# Speedy_V2_1.net
KiCad netlist of a schematic drawn in EAGLE
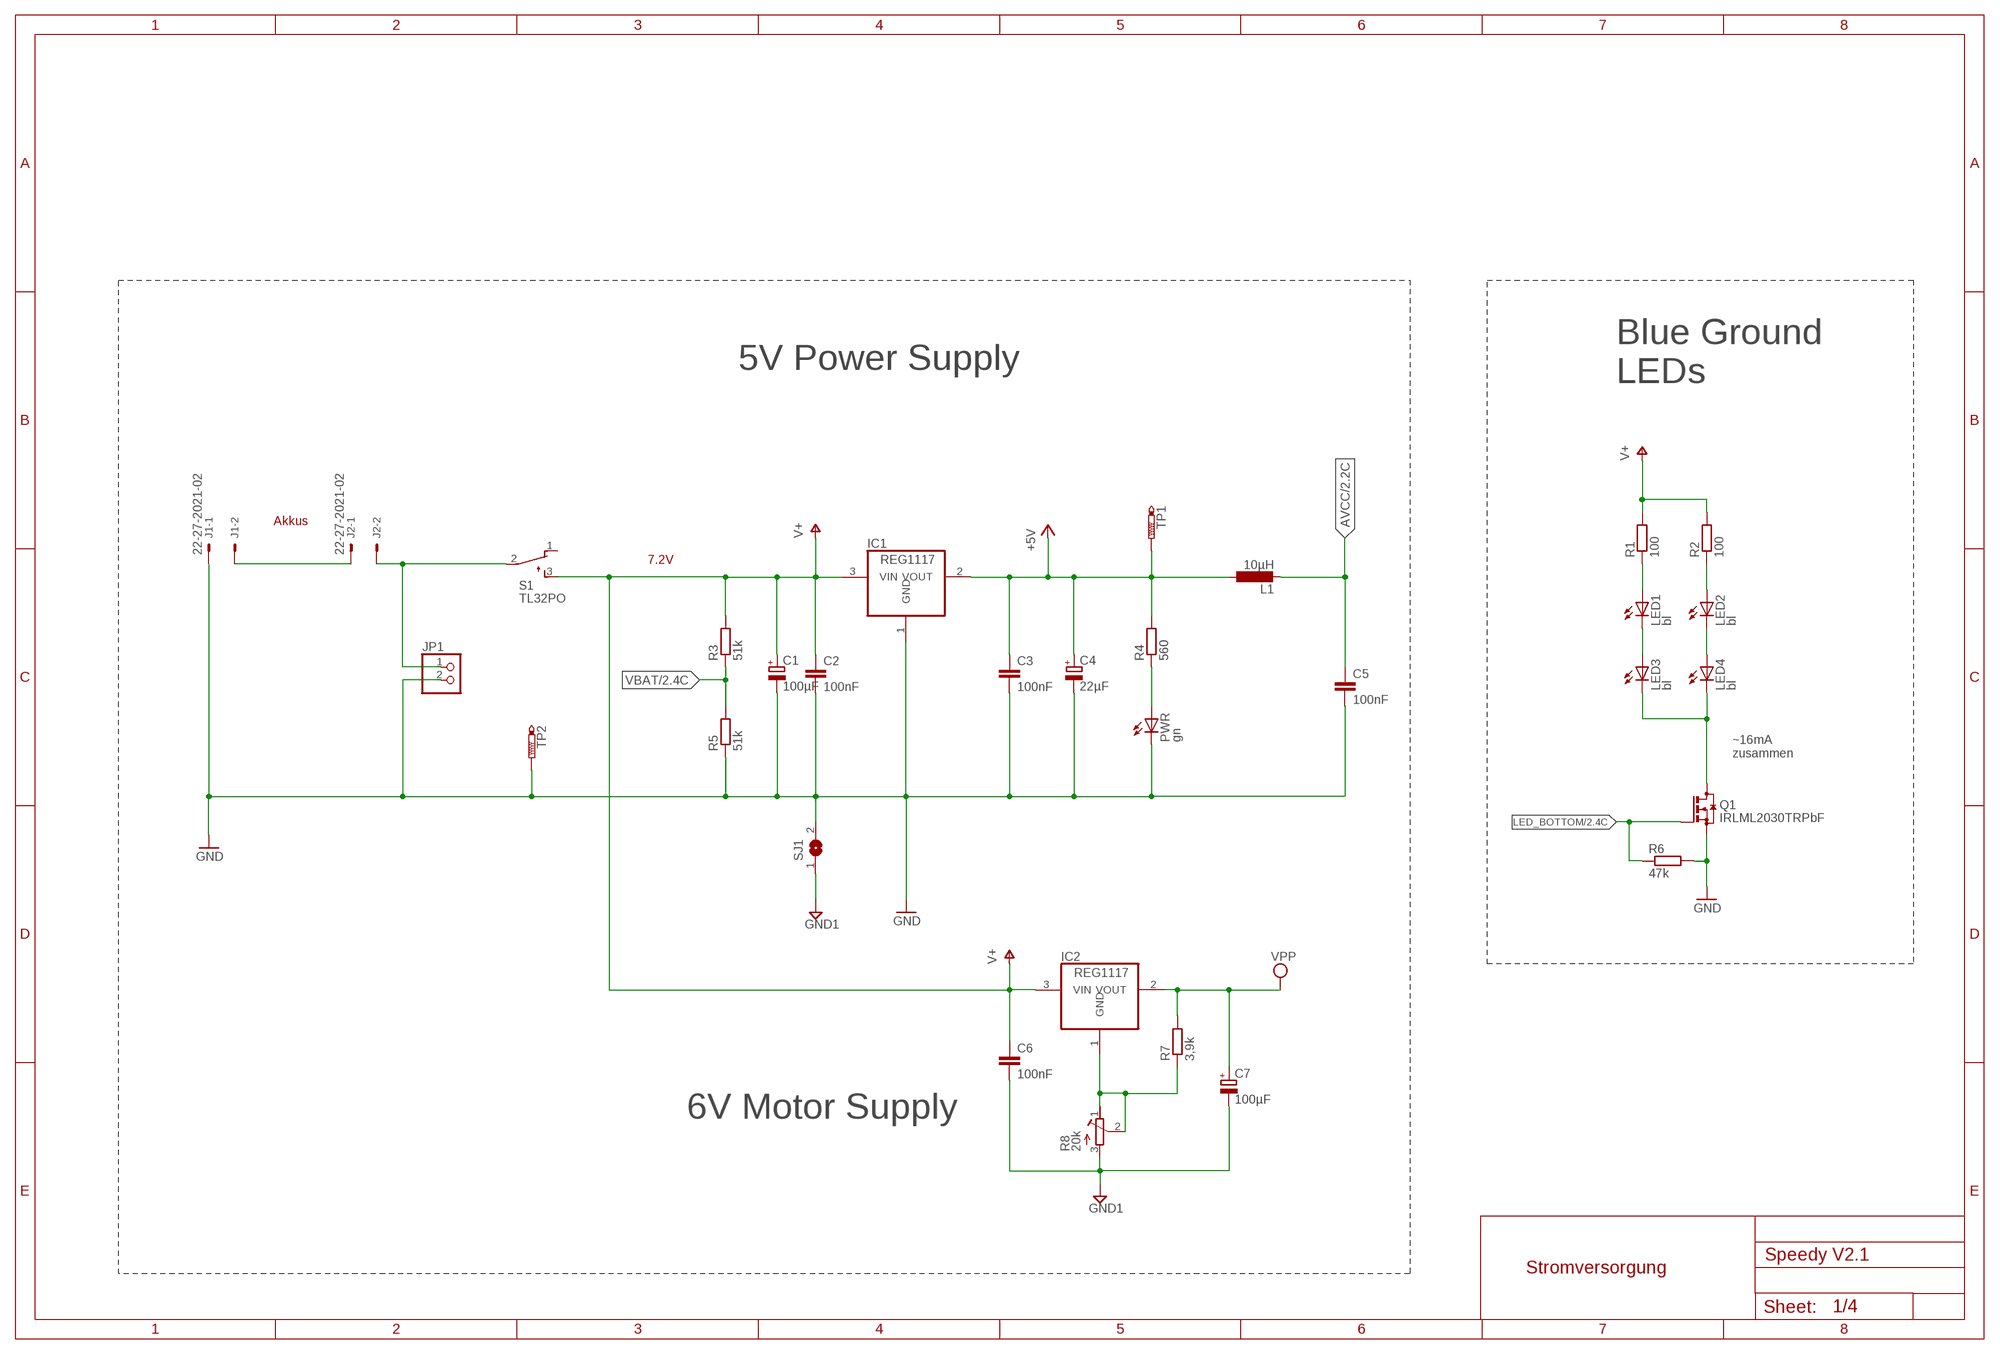
[diagram p0: schematic, sheet 1]
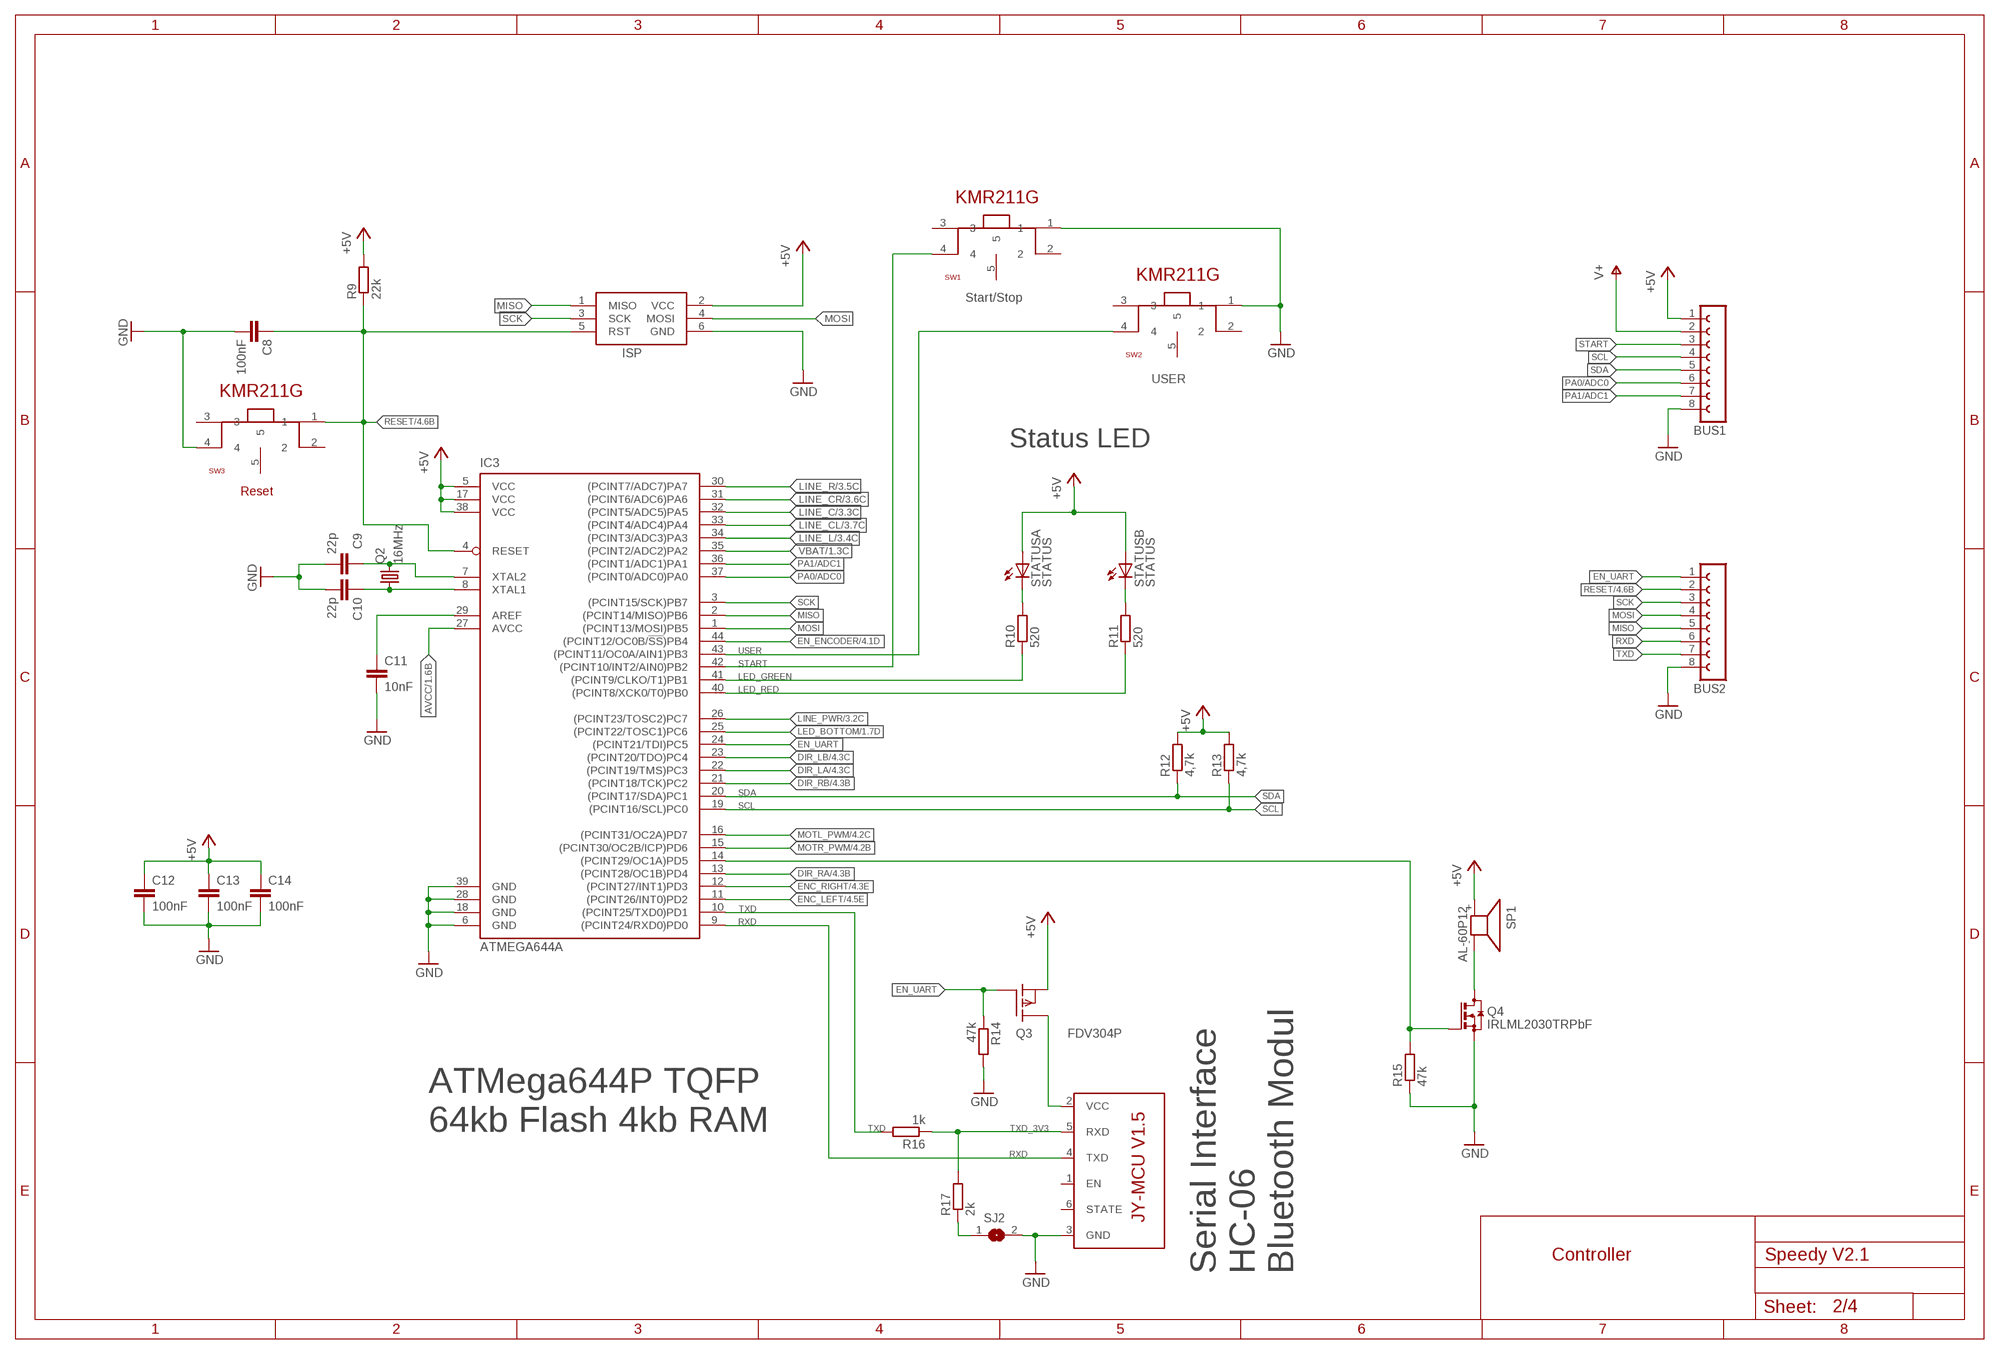
[diagram p1: schematic, sheet 2]
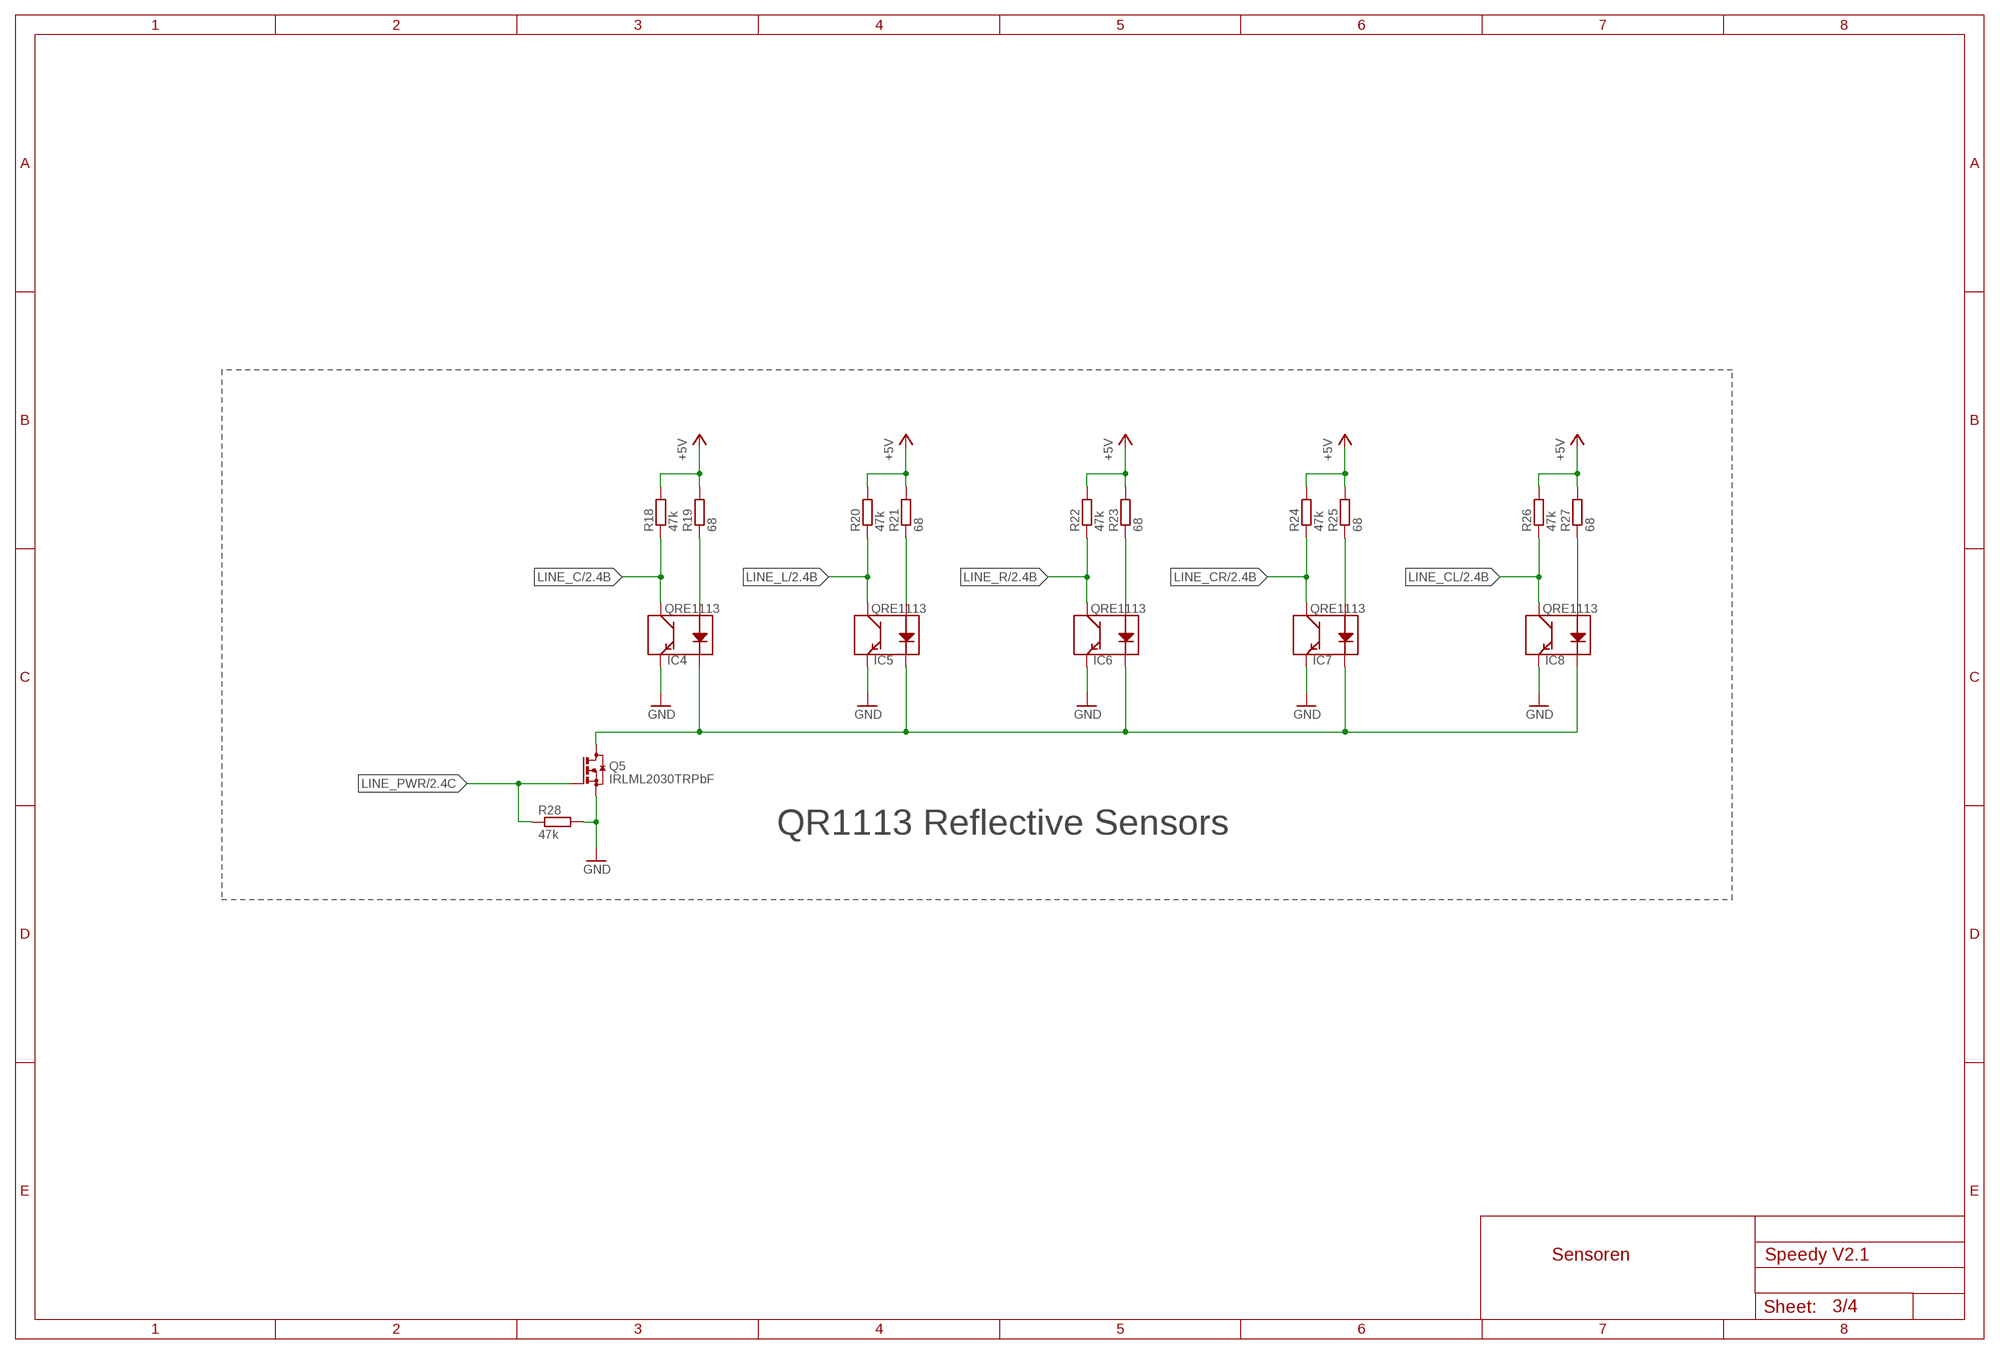
[diagram p2: schematic, sheet 3]
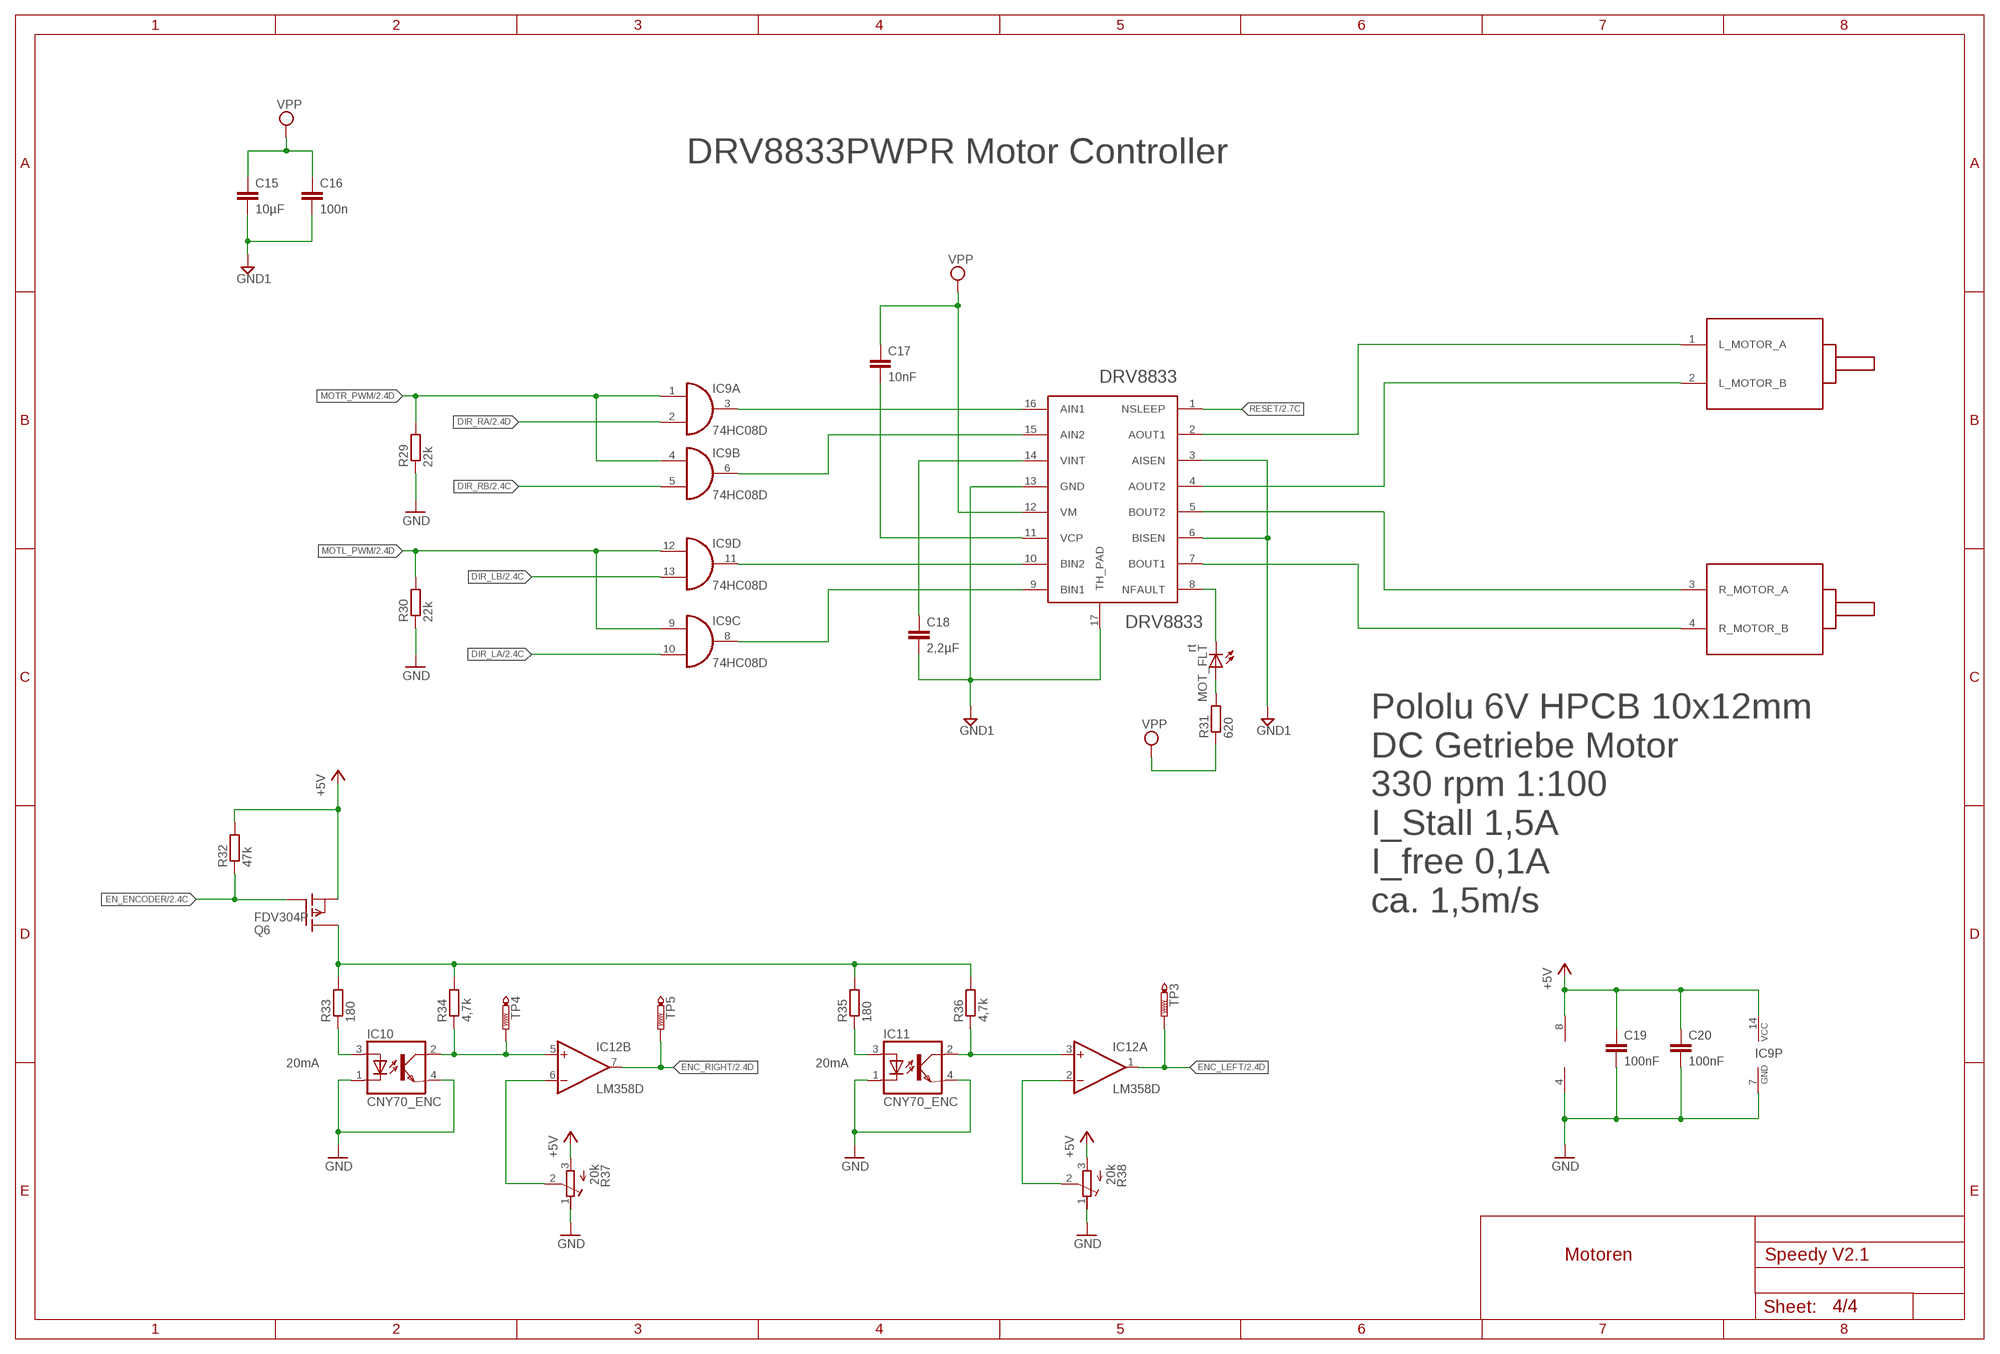
[diagram p3: schematic, sheet 4]

(export (version "E")
  (design (tool "Eeschema 10.0.6"))
  (components
    (comp (ref "BUS1")
      (value "FE08-1")
      (footprint "eagle-import:FE08")
      (libsource (lib "eagle-import") (part "FE08-1"))
    )
    (comp (ref "BUS2")
      (value "FE08-1")
      (footprint "eagle-import:FE08")
      (libsource (lib "eagle-import") (part "FE08-1"))
    )
    (comp (ref "C8")
      (value "100nF")
      (footprint "eagle-import:C0805")
      (libsource (lib "eagle-import") (part "C-EUC0805"))
    )
    (comp (ref "C9")
      (value "22p")
      (footprint "eagle-import:C0603")
      (libsource (lib "eagle-import") (part "C-EUC0603"))
    )
    (comp (ref "C10")
      (value "22p")
      (footprint "eagle-import:C0603")
      (libsource (lib "eagle-import") (part "C-EUC0603"))
    )
    (comp (ref "C11")
      (value "10nF")
      (footprint "eagle-import:C0603")
      (libsource (lib "eagle-import") (part "C-EUC0603"))
    )
    (comp (ref "C12")
      (value "100nF")
      (footprint "eagle-import:C0603")
      (libsource (lib "eagle-import") (part "C-EUC0603"))
    )
    (comp (ref "C13")
      (value "100nF")
      (footprint "eagle-import:C0603")
      (libsource (lib "eagle-import") (part "C-EUC0603"))
    )
    (comp (ref "C14")
      (value "100nF")
      (footprint "eagle-import:C0603")
      (libsource (lib "eagle-import") (part "C-EUC0603"))
    )
    (comp (ref "IC3")
      (value "ATMEGA644A")
      (footprint "eagle-import:TQFP44")
      (fields (field (name "MPN") "ATMEGA644PV-10AU"))
      (libsource (lib "eagle-import") (part "ATMEGA644A"))
    )
    (comp (ref "ISP")
      (value "AVRISP-6")
      (footprint "eagle-import:AVRISP")
      (libsource (lib "eagle-import") (part "AVRISP-6"))
    )
    (comp (ref "Q2")
      (value "16MHz")
      (footprint "eagle-import:7X5MMQUARZ")
      (libsource (lib "eagle-import") (part "7X5MMMQ"))
    )
    (comp (ref "Q3")
      (value "FDV304P")
      (footprint "eagle-import:SOT23")
      (libsource (lib "eagle-import") (part "FDV304P"))
    )
    (comp (ref "Q4")
      (value "IRLML2030TRPbF")
      (footprint "eagle-import:SOT23")
      (libsource (lib "eagle-import") (part "BSS123"))
    )
    (comp (ref "R9")
      (value "22k")
      (footprint "eagle-import:R0805")
      (libsource (lib "eagle-import") (part "R-EU_R0805"))
    )
    (comp (ref "R10")
      (value "520")
      (footprint "eagle-import:R0805")
      (libsource (lib "eagle-import") (part "R-EU_R0805"))
    )
    (comp (ref "R11")
      (value "520")
      (footprint "eagle-import:R0805")
      (libsource (lib "eagle-import") (part "R-EU_R0805"))
    )
    (comp (ref "R12")
      (value "4,7k")
      (footprint "eagle-import:R0805")
      (libsource (lib "eagle-import") (part "R-EU_R0805"))
    )
    (comp (ref "R13")
      (value "4,7k")
      (footprint "eagle-import:R0805")
      (libsource (lib "eagle-import") (part "R-EU_R0805"))
    )
    (comp (ref "R14")
      (value "47k")
      (footprint "eagle-import:R0805")
      (libsource (lib "eagle-import") (part "R-EU_R0805"))
    )
    (comp (ref "R15")
      (value "47k")
      (footprint "eagle-import:R0805")
      (libsource (lib "eagle-import") (part "R-EU_R0805"))
    )
    (comp (ref "R16")
      (value "1k")
      (footprint "eagle-import:R0805")
      (libsource (lib "eagle-import") (part "R-EU_R0805"))
    )
    (comp (ref "R17")
      (value "2k")
      (footprint "eagle-import:R0805")
      (libsource (lib "eagle-import") (part "R-EU_R0805"))
    )
    (comp (ref "SJ2") (value "SJ") (footprint "eagle-import:SJ") (libsource (lib "eagle-import") (part "SJ")))
    (comp (ref "SP1")
      (value "AL-60P12")
      (footprint "eagle-import:KSS1201")
      (libsource (lib "eagle-import") (part "KSS1201"))
    )
    (comp (ref "STATUS")
      (value "STATUS")
      (footprint "eagle-import:P-LCC4-0")
      (libsource (lib "eagle-import") (part "LSG-T676"))
    )
    (comp (ref "SW1")
      (value "KMR211G_SWITCH")
      (footprint "eagle-import:KMR211G_SWITCH")
      (libsource (lib "eagle-import") (part "KMR211G_SWITCH"))
    )
    (comp (ref "SW2")
      (value "KMR211G_SWITCH")
      (footprint "eagle-import:KMR211G_SWITCH")
      (libsource (lib "eagle-import") (part "KMR211G_SWITCH"))
    )
    (comp (ref "SW3")
      (value "KMR211G_SWITCH")
      (footprint "eagle-import:KMR211G_SWITCH")
      (libsource (lib "eagle-import") (part "KMR211G_SWITCH"))
    )
    (comp (ref "U1")
      (value "BT_BOARD")
      (footprint "eagle-import:BT_BOARD")
      (libsource (lib "eagle-import") (part "BT_BOARD"))
    )
    (comp (ref "C1")
      (value "100µF")
      (footprint "eagle-import:PANASONIC_D")
      (libsource (lib "eagle-import") (part "CPOL-EUD"))
    )
    (comp (ref "C2")
      (value "100nF")
      (footprint "eagle-import:C0805")
      (libsource (lib "eagle-import") (part "C-EUC0805"))
    )
    (comp (ref "C3")
      (value "100nF")
      (footprint "eagle-import:C0805")
      (libsource (lib "eagle-import") (part "C-EUC0805"))
    )
    (comp (ref "C4")
      (value "22µF")
      (footprint "eagle-import:PANASONIC_B")
      (libsource (lib "eagle-import") (part "CPOL-EUB"))
    )
    (comp (ref "C5")
      (value "100nF")
      (footprint "eagle-import:C0805")
      (libsource (lib "eagle-import") (part "C-EUC0805"))
    )
    (comp (ref "C6")
      (value "100nF")
      (footprint "eagle-import:C0805")
      (libsource (lib "eagle-import") (part "C-EUC0805"))
    )
    (comp (ref "C7")
      (value "100µF")
      (footprint "eagle-import:PANASONIC_D")
      (libsource (lib "eagle-import") (part "CPOL-EUD"))
    )
    (comp (ref "IC1")
      (value "REG1117")
      (footprint "eagle-import:SOT223")
      (libsource (lib "eagle-import") (part "REG1117"))
    )
    (comp (ref "IC2")
      (value "REG1117")
      (footprint "eagle-import:SOT223")
      (libsource (lib "eagle-import") (part "REG1117"))
    )
    (comp (ref "J1")
      (value "22-27-2021-02")
      (footprint "eagle-import:6410-02")
      (libsource (lib "eagle-import") (part "22-?-0227-2021"))
    )
    (comp (ref "J2")
      (value "22-27-2021-02")
      (footprint "eagle-import:6410-02")
      (libsource (lib "eagle-import") (part "22-?-0227-2021"))
    )
    (comp (ref "JP1")
      (value "PINHD-1X2")
      (footprint "eagle-import:1X02")
      (libsource (lib "eagle-import") (part "PINHD-1X2"))
    )
    (comp (ref "L1")
      (value "10µH")
      (footprint "eagle-import:C1210K")
      (libsource (lib "eagle-import") (part "L-1210"))
    )
    (comp (ref "LED1")
      (value "bl")
      (footprint "eagle-import:CHIPLED_0805")
      (libsource (lib "eagle-import") (part "LEDCHIPLED_0805"))
    )
    (comp (ref "LED2")
      (value "bl")
      (footprint "eagle-import:CHIPLED_0805")
      (libsource (lib "eagle-import") (part "LEDCHIPLED_0805"))
    )
    (comp (ref "LED3")
      (value "bl")
      (footprint "eagle-import:CHIPLED_0805")
      (libsource (lib "eagle-import") (part "LEDCHIPLED_0805"))
    )
    (comp (ref "LED4")
      (value "bl")
      (footprint "eagle-import:CHIPLED_0805")
      (libsource (lib "eagle-import") (part "LEDCHIPLED_0805"))
    )
    (comp (ref "PWR")
      (value "gn")
      (footprint "eagle-import:CHIPLED_0805")
      (libsource (lib "eagle-import") (part "LEDCHIPLED_0805"))
    )
    (comp (ref "Q1")
      (value "IRLML2030TRPbF")
      (footprint "eagle-import:SOT23")
      (libsource (lib "eagle-import") (part "BSS123"))
    )
    (comp (ref "R1")
      (value "100")
      (footprint "eagle-import:R0805")
      (libsource (lib "eagle-import") (part "R-EU_R0805"))
    )
    (comp (ref "R2")
      (value "100")
      (footprint "eagle-import:R0805")
      (libsource (lib "eagle-import") (part "R-EU_R0805"))
    )
    (comp (ref "R3")
      (value "51k")
      (footprint "eagle-import:R0805")
      (libsource (lib "eagle-import") (part "R-EU_R0805"))
    )
    (comp (ref "R4")
      (value "560")
      (footprint "eagle-import:R0805")
      (libsource (lib "eagle-import") (part "R-EU_R0805"))
    )
    (comp (ref "R5")
      (value "51k")
      (footprint "eagle-import:R0805")
      (libsource (lib "eagle-import") (part "R-EU_R0805"))
    )
    (comp (ref "R6")
      (value "47k")
      (footprint "eagle-import:R0805")
      (libsource (lib "eagle-import") (part "R-EU_R0805"))
    )
    (comp (ref "R7")
      (value "3,9k")
      (footprint "eagle-import:R0805")
      (libsource (lib "eagle-import") (part "R-EU_R0805"))
    )
    (comp (ref "R8")
      (value "20k")
      (footprint "eagle-import:RTRIM3314G")
      (libsource (lib "eagle-import") (part "R-TRIMM3314G"))
    )
    (comp (ref "S1")
      (value "TL32PO")
      (footprint "eagle-import:TL3XPO")
      (libsource (lib "eagle-import") (part "TL32PO"))
    )
    (comp (ref "SJ1") (value "SJ") (footprint "eagle-import:SJ") (libsource (lib "eagle-import") (part "SJ")))
    (comp (ref "TP1")
      (value "PTR1B1,27")
      (footprint "eagle-import:B1,27")
      (libsource (lib "eagle-import") (part "PTR1B1,27"))
    )
    (comp (ref "TP2")
      (value "PTR1PAD1-13")
      (footprint "eagle-import:P1-13")
      (libsource (lib "eagle-import") (part "PTR1PAD1-13"))
    )
    (comp (ref "C15")
      (value "10µF")
      (footprint "eagle-import:C1206")
      (libsource (lib "eagle-import") (part "C-EUC1206"))
    )
    (comp (ref "C16")
      (value "100n")
      (footprint "eagle-import:C0805")
      (libsource (lib "eagle-import") (part "C-EUC0805"))
    )
    (comp (ref "C17")
      (value "10nF")
      (footprint "eagle-import:C0805")
      (libsource (lib "eagle-import") (part "C-EUC0805"))
    )
    (comp (ref "C18")
      (value "2,2µF")
      (footprint "eagle-import:C1206")
      (libsource (lib "eagle-import") (part "C-EUC1206"))
    )
    (comp (ref "C19")
      (value "100nF")
      (footprint "eagle-import:C0805")
      (libsource (lib "eagle-import") (part "C-EUC0805"))
    )
    (comp (ref "C20")
      (value "100nF")
      (footprint "eagle-import:C0805")
      (libsource (lib "eagle-import") (part "C-EUC0805"))
    )
    (comp (ref "IC9")
      (value "74HC08D")
      (footprint "eagle-import:SO14")
      (libsource (lib "eagle-import") (part "7408DHC"))
    )
    (comp (ref "IC10")
      (value "CNY70_ENC")
      (footprint "eagle-import:CNY70_ENC")
      (libsource (lib "eagle-import") (part "CNY70_ENC"))
    )
    (comp (ref "IC11")
      (value "CNY70_ENC")
      (footprint "eagle-import:CNY70_ENC")
      (libsource (lib "eagle-import") (part "CNY70_ENC"))
    )
    (comp (ref "IC12")
      (value "LM358D")
      (footprint "eagle-import:SO08")
      (libsource (lib "eagle-import") (part "LM358D"))
    )
    (comp (ref "MOT_FLT")
      (value "rt")
      (footprint "eagle-import:CHIP-LED0805")
      (libsource (lib "eagle-import") (part "LEDCHIP-LED0805"))
    )
    (comp (ref "Q6")
      (value "FDV304P")
      (footprint "eagle-import:SOT23")
      (libsource (lib "eagle-import") (part "FDV304P"))
    )
    (comp (ref "R29")
      (value "22k")
      (footprint "eagle-import:R0805")
      (libsource (lib "eagle-import") (part "R-EU_R0805"))
    )
    (comp (ref "R30")
      (value "22k")
      (footprint "eagle-import:R0805")
      (libsource (lib "eagle-import") (part "R-EU_R0805"))
    )
    (comp (ref "R31")
      (value "620")
      (footprint "eagle-import:R0805")
      (libsource (lib "eagle-import") (part "R-EU_R0805"))
    )
    (comp (ref "R32")
      (value "47k")
      (footprint "eagle-import:R0805")
      (libsource (lib "eagle-import") (part "R-EU_R0805"))
    )
    (comp (ref "R33")
      (value "180")
      (footprint "eagle-import:R0805")
      (libsource (lib "eagle-import") (part "R-EU_R0805"))
    )
    (comp (ref "R34")
      (value "4,7k")
      (footprint "eagle-import:R0805")
      (libsource (lib "eagle-import") (part "R-EU_R0805"))
    )
    (comp (ref "R35")
      (value "180")
      (footprint "eagle-import:R0805")
      (libsource (lib "eagle-import") (part "R-EU_R0805"))
    )
    (comp (ref "R36")
      (value "4,7k")
      (footprint "eagle-import:R0805")
      (libsource (lib "eagle-import") (part "R-EU_R0805"))
    )
    (comp (ref "R37")
      (value "20k")
      (footprint "eagle-import:RTRIM3314G")
      (libsource (lib "eagle-import") (part "R-TRIMM3314G"))
    )
    (comp (ref "R38")
      (value "20k")
      (footprint "eagle-import:RTRIM3314G")
      (libsource (lib "eagle-import") (part "R-TRIMM3314G"))
    )
    (comp (ref "TP3")
      (value "PTR1B1,27")
      (footprint "eagle-import:B1,27")
      (libsource (lib "eagle-import") (part "PTR1B1,27"))
    )
    (comp (ref "TP4")
      (value "PTR1B1,27")
      (footprint "eagle-import:B1,27")
      (libsource (lib "eagle-import") (part "PTR1B1,27"))
    )
    (comp (ref "TP5")
      (value "PTR1B1,27")
      (footprint "eagle-import:B1,27")
      (libsource (lib "eagle-import") (part "PTR1B1,27"))
    )
    (comp (ref "U$1")
      (value "SPEEDY_MOTOR_MOUNT")
      (footprint "eagle-import:FUTURA_V1.0_MOTOT_MOUNT")
      (libsource (lib "eagle-import") (part "SPEEDY_MOTOR_MOUNT"))
    )
    (comp (ref "U2")
      (value "DRV8833")
      (footprint "eagle-import:SOP65P640X120-17N")
      (libsource (lib "eagle-import") (part "DRV8833"))
    )
    (comp (ref "IC4")
      (value "QRE1113")
      (footprint "eagle-import:QRE1113")
      (libsource (lib "eagle-import") (part "QRE1113"))
    )
    (comp (ref "IC5")
      (value "QRE1113")
      (footprint "eagle-import:QRE1113")
      (libsource (lib "eagle-import") (part "QRE1113"))
    )
    (comp (ref "IC6")
      (value "QRE1113")
      (footprint "eagle-import:QRE1113")
      (libsource (lib "eagle-import") (part "QRE1113"))
    )
    (comp (ref "IC7")
      (value "QRE1113")
      (footprint "eagle-import:QRE1113")
      (libsource (lib "eagle-import") (part "QRE1113"))
    )
    (comp (ref "IC8")
      (value "QRE1113")
      (footprint "eagle-import:QRE1113")
      (libsource (lib "eagle-import") (part "QRE1113"))
    )
    (comp (ref "Q5")
      (value "IRLML2030TRPbF")
      (footprint "eagle-import:SOT23")
      (libsource (lib "eagle-import") (part "BSS123"))
    )
    (comp (ref "R18")
      (value "47k")
      (footprint "eagle-import:R0805")
      (libsource (lib "eagle-import") (part "R-EU_R0805"))
    )
    (comp (ref "R19")
      (value "68")
      (footprint "eagle-import:R0805")
      (libsource (lib "eagle-import") (part "R-EU_R0805"))
    )
    (comp (ref "R20")
      (value "47k")
      (footprint "eagle-import:R0805")
      (libsource (lib "eagle-import") (part "R-EU_R0805"))
    )
    (comp (ref "R21")
      (value "68")
      (footprint "eagle-import:R0805")
      (libsource (lib "eagle-import") (part "R-EU_R0805"))
    )
    (comp (ref "R22")
      (value "47k")
      (footprint "eagle-import:R0805")
      (libsource (lib "eagle-import") (part "R-EU_R0805"))
    )
    (comp (ref "R23")
      (value "68")
      (footprint "eagle-import:R0805")
      (libsource (lib "eagle-import") (part "R-EU_R0805"))
    )
    (comp (ref "R24")
      (value "47k")
      (footprint "eagle-import:R0805")
      (libsource (lib "eagle-import") (part "R-EU_R0805"))
    )
    (comp (ref "R25")
      (value "68")
      (footprint "eagle-import:R0805")
      (libsource (lib "eagle-import") (part "R-EU_R0805"))
    )
    (comp (ref "R26")
      (value "47k")
      (footprint "eagle-import:R0805")
      (libsource (lib "eagle-import") (part "R-EU_R0805"))
    )
    (comp (ref "R27")
      (value "68")
      (footprint "eagle-import:R0805")
      (libsource (lib "eagle-import") (part "R-EU_R0805"))
    )
    (comp (ref "R28")
      (value "47k")
      (footprint "eagle-import:R0805")
      (libsource (lib "eagle-import") (part "R-EU_R0805"))
    )
  )
  (nets
    (net (code "1") (name "+5V") (class "Default")
      (node (ref "BUS1") (pin "1") (pinfunction "1_1") (pintype "passive"))
      (node (ref "C12") (pin "1") (pinfunction "1_1") (pintype "passive"))
      (node (ref "C13") (pin "1") (pinfunction "1_1") (pintype "passive"))
      (node (ref "C14") (pin "1") (pinfunction "1_1") (pintype "passive"))
      (node (ref "C19") (pin "1") (pinfunction "1_1") (pintype "passive"))
      (node (ref "C20") (pin "1") (pinfunction "1_1") (pintype "passive"))
      (node (ref "C3") (pin "1") (pinfunction "1_1") (pintype "passive"))
      (node (ref "C4") (pin "+") (pinfunction "+_+") (pintype "passive"))
      (node (ref "IC1") (pin "2") (pinfunction "VOUT_2") (pintype "output"))
      (node (ref "IC12") (pin "8") (pinfunction "V+_8") (pintype "power_in"))
      (node (ref "IC3") (pin "17") (pinfunction "VCC_17") (pintype "power_in"))
      (node (ref "IC3") (pin "38") (pinfunction "VCC_38") (pintype "power_in"))
      (node (ref "IC3") (pin "5") (pinfunction "VCC_5") (pintype "power_in"))
      (node (ref "IC9") (pin "14") (pinfunction "VCC_14") (pintype "power_in"))
      (node (ref "ISP") (pin "2") (pinfunction "VCC_2") (pintype "power_in"))
      (node (ref "L1") (pin "1") (pinfunction "1_1") (pintype "passive"))
      (node (ref "Q3") (pin "S") (pinfunction "S_S") (pintype "passive"))
      (node (ref "Q6") (pin "S") (pinfunction "S_S") (pintype "passive"))
      (node (ref "R12") (pin "2") (pinfunction "2_2") (pintype "passive"))
      (node (ref "R13") (pin "2") (pinfunction "2_2") (pintype "passive"))
      (node (ref "R18") (pin "2") (pinfunction "2_2") (pintype "passive"))
      (node (ref "R19") (pin "2") (pinfunction "2_2") (pintype "passive"))
      (node (ref "R20") (pin "2") (pinfunction "2_2") (pintype "passive"))
      (node (ref "R21") (pin "2") (pinfunction "2_2") (pintype "passive"))
      (node (ref "R22") (pin "2") (pinfunction "2_2") (pintype "passive"))
      (node (ref "R23") (pin "2") (pinfunction "2_2") (pintype "passive"))
      (node (ref "R24") (pin "2") (pinfunction "2_2") (pintype "passive"))
      (node (ref "R25") (pin "2") (pinfunction "2_2") (pintype "passive"))
      (node (ref "R26") (pin "2") (pinfunction "2_2") (pintype "passive"))
      (node (ref "R27") (pin "2") (pinfunction "2_2") (pintype "passive"))
      (node (ref "R32") (pin "2") (pinfunction "2_2") (pintype "passive"))
      (node (ref "R37") (pin "3") (pinfunction "A_3") (pintype "passive"))
      (node (ref "R38") (pin "3") (pinfunction "A_3") (pintype "passive"))
      (node (ref "R4") (pin "2") (pinfunction "2_2") (pintype "passive"))
      (node (ref "R9") (pin "2") (pinfunction "2_2") (pintype "passive"))
      (node (ref "SP1") (pin "+") (pinfunction "1_+") (pintype "passive"))
      (node (ref "STATUS") (pin "2") (pinfunction "A_2") (pintype "passive"))
      (node (ref "STATUS") (pin "4") (pinfunction "A_4") (pintype "passive"))
      (node (ref "TP1") (pin "TP") (pinfunction "TP_TP") (pintype "input"))
    )
    (net (code "2") (name "AVCC") (class "Default")
      (node (ref "C5") (pin "1") (pinfunction "1_1") (pintype "passive"))
      (node (ref "IC3") (pin "27") (pinfunction "AVCC_27") (pintype "power_in"))
      (node (ref "L1") (pin "2") (pinfunction "2_2") (pintype "passive"))
    )
    (net (code "3") (name "DIR_LA") (class "Default")
      (node (ref "IC3") (pin "22") (pinfunction "(PCINT19/TMS)PC3_22") (pintype "output"))
      (node (ref "IC9") (pin "10") (pinfunction "I1_10") (pintype "input"))
    )
    (net (code "4") (name "DIR_LB") (class "Default")
      (node (ref "IC3") (pin "23") (pinfunction "(PCINT20/TDO)PC4_23") (pintype "output"))
      (node (ref "IC9") (pin "13") (pinfunction "I1_13") (pintype "input"))
    )
    (net (code "5") (name "DIR_RA") (class "Default")
      (node (ref "IC3") (pin "13") (pinfunction "(PCINT28/OC1B)PD4_13") (pintype "bidirectional"))
      (node (ref "IC9") (pin "2") (pinfunction "I1_2") (pintype "input"))
    )
    (net (code "6") (name "DIR_RB") (class "Default")
      (node (ref "IC3") (pin "21") (pinfunction "(PCINT18/TCK)PC2_21") (pintype "output"))
      (node (ref "IC9") (pin "5") (pinfunction "I1_5") (pintype "input"))
    )
    (net (code "7") (name "ENC_LEFT") (class "Default")
      (node (ref "IC12") (pin "1") (pinfunction "OUT_1") (pintype "output"))
      (node (ref "IC3") (pin "11") (pinfunction "(PCINT26/INT0)PD2_11") (pintype "bidirectional"))
      (node (ref "TP3") (pin "TP") (pinfunction "TP_TP") (pintype "input"))
    )
    (net (code "8") (name "ENC_RIGHT") (class "Default")
      (node (ref "IC12") (pin "7") (pinfunction "OUT_7") (pintype "output"))
      (node (ref "IC3") (pin "12") (pinfunction "(PCINT27/INT1)PD3_12") (pintype "bidirectional"))
      (node (ref "TP5") (pin "TP") (pinfunction "TP_TP") (pintype "input"))
    )
    (net (code "9") (name "EN_ENCODER") (class "Default")
      (node (ref "IC3") (pin "44") (pinfunction "(PCINT12/OC0B/~{SS})PB4_44") (pintype "bidirectional"))
      (node (ref "Q6") (pin "G") (pinfunction "G_G") (pintype "passive"))
      (node (ref "R32") (pin "1") (pinfunction "1_1") (pintype "passive"))
    )
    (net (code "10") (name "EN_UART") (class "Default")
      (node (ref "BUS2") (pin "1") (pinfunction "1_1") (pintype "passive"))
      (node (ref "IC3") (pin "24") (pinfunction "(PCINT21/TDI)PC5_24") (pintype "output"))
      (node (ref "Q3") (pin "G") (pinfunction "G_G") (pintype "passive"))
      (node (ref "R14") (pin "1") (pinfunction "1_1") (pintype "passive"))
    )
    (net (code "11") (name "GND") (class "Default")
      (node (ref "BUS1") (pin "8") (pinfunction "8_8") (pintype "passive"))
      (node (ref "BUS2") (pin "8") (pinfunction "8_8") (pintype "passive"))
      (node (ref "C1") (pin "-") (pinfunction "-_-") (pintype "passive"))
      (node (ref "C10") (pin "2") (pinfunction "2_2") (pintype "passive"))
      (node (ref "C11") (pin "2") (pinfunction "2_2") (pintype "passive"))
      (node (ref "C12") (pin "2") (pinfunction "2_2") (pintype "passive"))
      (node (ref "C13") (pin "2") (pinfunction "2_2") (pintype "passive"))
      (node (ref "C14") (pin "2") (pinfunction "2_2") (pintype "passive"))
      (node (ref "C19") (pin "2") (pinfunction "2_2") (pintype "passive"))
      (node (ref "C2") (pin "2") (pinfunction "2_2") (pintype "passive"))
      (node (ref "C20") (pin "2") (pinfunction "2_2") (pintype "passive"))
      (node (ref "C3") (pin "2") (pinfunction "2_2") (pintype "passive"))
      (node (ref "C4") (pin "-") (pinfunction "-_-") (pintype "passive"))
      (node (ref "C5") (pin "2") (pinfunction "2_2") (pintype "passive"))
      (node (ref "C8") (pin "2") (pinfunction "2_2") (pintype "passive"))
      (node (ref "C9") (pin "2") (pinfunction "2_2") (pintype "passive"))
      (node (ref "IC1") (pin "1") (pinfunction "GND_1") (pintype "power_in"))
      (node (ref "IC10") (pin "1") (pinfunction "CATH._1") (pintype "passive"))
      (node (ref "IC10") (pin "4") (pinfunction "E_4") (pintype "passive"))
      (node (ref "IC11") (pin "1") (pinfunction "CATH._1") (pintype "passive"))
      (node (ref "IC11") (pin "4") (pinfunction "E_4") (pintype "passive"))
      (node (ref "IC12") (pin "4") (pinfunction "V-_4") (pintype "power_in"))
      (node (ref "IC3") (pin "18") (pinfunction "GND_18") (pintype "power_in"))
      (node (ref "IC3") (pin "28") (pinfunction "GND_28") (pintype "power_in"))
      (node (ref "IC3") (pin "39") (pinfunction "GND_39") (pintype "power_in"))
      (node (ref "IC3") (pin "6") (pinfunction "GND_6") (pintype "power_in"))
      (node (ref "IC4") (pin "4") (pinfunction "E_4") (pintype "bidirectional"))
      (node (ref "IC5") (pin "4") (pinfunction "E_4") (pintype "bidirectional"))
      (node (ref "IC6") (pin "4") (pinfunction "E_4") (pintype "bidirectional"))
      (node (ref "IC7") (pin "4") (pinfunction "E_4") (pintype "bidirectional"))
      (node (ref "IC8") (pin "4") (pinfunction "E_4") (pintype "bidirectional"))
      (node (ref "IC9") (pin "7") (pinfunction "GND_7") (pintype "power_in"))
      (node (ref "ISP") (pin "6") (pinfunction "GND_6") (pintype "power_in"))
      (node (ref "J1") (pin "1") (pinfunction "S_1") (pintype "passive"))
      (node (ref "JP1") (pin "2") (pinfunction "2_2") (pintype "passive"))
      (node (ref "PWR") (pin "C") (pinfunction "C_C") (pintype "passive"))
      (node (ref "Q1") (pin "2") (pinfunction "S_2") (pintype "passive"))
      (node (ref "Q4") (pin "2") (pinfunction "S_2") (pintype "passive"))
      (node (ref "Q5") (pin "2") (pinfunction "S_2") (pintype "passive"))
      (node (ref "R14") (pin "2") (pinfunction "2_2") (pintype "passive"))
      (node (ref "R15") (pin "1") (pinfunction "1_1") (pintype "passive"))
      (node (ref "R28") (pin "2") (pinfunction "2_2") (pintype "passive"))
      (node (ref "R29") (pin "1") (pinfunction "1_1") (pintype "passive"))
      (node (ref "R30") (pin "1") (pinfunction "1_1") (pintype "passive"))
      (node (ref "R37") (pin "1") (pinfunction "E_1") (pintype "passive"))
      (node (ref "R38") (pin "1") (pinfunction "E_1") (pintype "passive"))
      (node (ref "R5") (pin "1") (pinfunction "1_1") (pintype "passive"))
      (node (ref "R6") (pin "2") (pinfunction "2_2") (pintype "passive"))
      (node (ref "SJ1") (pin "2") (pinfunction "2_2") (pintype "passive"))
      (node (ref "SJ2") (pin "2") (pinfunction "2_2") (pintype "passive"))
      (node (ref "SW1") (pin "1") (pinfunction "1_1") (pintype "bidirectional"))
      (node (ref "SW2") (pin "1") (pinfunction "1_1") (pintype "bidirectional"))
      (node (ref "SW3") (pin "4") (pinfunction "4_4") (pintype "bidirectional"))
      (node (ref "TP2") (pin "TP") (pinfunction "TP_TP") (pintype "input"))
      (node (ref "U1") (pin "3") (pinfunction "GND_3") (pintype "bidirectional"))
    )
    (net (code "12") (name "GND1") (class "Default")
      (node (ref "C15") (pin "2") (pinfunction "2_2") (pintype "passive"))
      (node (ref "C16") (pin "2") (pinfunction "2_2") (pintype "passive"))
      (node (ref "C18") (pin "2") (pinfunction "2_2") (pintype "passive"))
      (node (ref "C6") (pin "2") (pinfunction "2_2") (pintype "passive"))
      (node (ref "C7") (pin "-") (pinfunction "-_-") (pintype "passive"))
      (node (ref "R8") (pin "3") (pinfunction "A_3") (pintype "passive"))
      (node (ref "SJ1") (pin "1") (pinfunction "1_1") (pintype "passive"))
      (node (ref "U2") (pin "13") (pinfunction "GND_13") (pintype "bidirectional"))
      (node (ref "U2") (pin "17") (pinfunction "TH_PAD_17") (pintype "bidirectional"))
      (node (ref "U2") (pin "3") (pinfunction "AISEN_3") (pintype "bidirectional"))
      (node (ref "U2") (pin "6") (pinfunction "BISEN_6") (pintype "bidirectional"))
    )
    (net (code "13") (name "LED_BOTTOM") (class "Default")
      (node (ref "IC3") (pin "25") (pinfunction "(PCINT22/TOSC1)PC6_25") (pintype "output"))
      (node (ref "Q1") (pin "1") (pinfunction "G_1") (pintype "passive"))
      (node (ref "R6") (pin "1") (pinfunction "1_1") (pintype "passive"))
    )
    (net (code "14") (name "LED_GREEN") (class "Default")
      (node (ref "IC3") (pin "41") (pinfunction "(PCINT9/CLKO/T1)PB1_41") (pintype "bidirectional"))
      (node (ref "R10") (pin "1") (pinfunction "1_1") (pintype "passive"))
    )
    (net (code "15") (name "LED_RED") (class "Default")
      (node (ref "IC3") (pin "40") (pinfunction "(PCINT8/XCK0/T0)PB0_40") (pintype "bidirectional"))
      (node (ref "R11") (pin "1") (pinfunction "1_1") (pintype "passive"))
    )
    (net (code "16") (name "LINE_C") (class "Default")
      (node (ref "IC3") (pin "32") (pinfunction "(PCINT5/ADC5)PA5_32") (pintype "bidirectional"))
      (node (ref "IC4") (pin "3") (pinfunction "C_3") (pintype "bidirectional"))
      (node (ref "R18") (pin "1") (pinfunction "1_1") (pintype "passive"))
    )
    (net (code "17") (name "LINE_CL") (class "Default")
      (node (ref "IC3") (pin "33") (pinfunction "(PCINT4/ADC4)PA4_33") (pintype "bidirectional"))
      (node (ref "IC8") (pin "3") (pinfunction "C_3") (pintype "bidirectional"))
      (node (ref "R26") (pin "1") (pinfunction "1_1") (pintype "passive"))
    )
    (net (code "18") (name "LINE_CR") (class "Default")
      (node (ref "IC3") (pin "31") (pinfunction "(PCINT6/ADC6)PA6_31") (pintype "bidirectional"))
      (node (ref "IC7") (pin "3") (pinfunction "C_3") (pintype "bidirectional"))
      (node (ref "R24") (pin "1") (pinfunction "1_1") (pintype "passive"))
    )
    (net (code "19") (name "LINE_L") (class "Default")
      (node (ref "IC3") (pin "34") (pinfunction "(PCINT3/ADC3)PA3_34") (pintype "bidirectional"))
      (node (ref "IC5") (pin "3") (pinfunction "C_3") (pintype "bidirectional"))
      (node (ref "R20") (pin "1") (pinfunction "1_1") (pintype "passive"))
    )
    (net (code "20") (name "LINE_PWR") (class "Default")
      (node (ref "IC3") (pin "26") (pinfunction "(PCINT23/TOSC2)PC7_26") (pintype "output"))
      (node (ref "Q5") (pin "1") (pinfunction "G_1") (pintype "passive"))
      (node (ref "R28") (pin "1") (pinfunction "1_1") (pintype "passive"))
    )
    (net (code "21") (name "LINE_R") (class "Default")
      (node (ref "IC3") (pin "30") (pinfunction "(PCINT7/ADC7)PA7_30") (pintype "bidirectional"))
      (node (ref "IC6") (pin "3") (pinfunction "C_3") (pintype "bidirectional"))
      (node (ref "R22") (pin "1") (pinfunction "1_1") (pintype "passive"))
    )
    (net (code "22") (name "MISO") (class "Default")
      (node (ref "BUS2") (pin "5") (pinfunction "5_5") (pintype "passive"))
      (node (ref "IC3") (pin "2") (pinfunction "(PCINT14/MISO)PB6_2") (pintype "bidirectional"))
      (node (ref "ISP") (pin "1") (pinfunction "MISO_1") (pintype "input"))
    )
    (net (code "23") (name "MOSI") (class "Default")
      (node (ref "BUS2") (pin "4") (pinfunction "4_4") (pintype "passive"))
      (node (ref "IC3") (pin "1") (pinfunction "(PCINT13/MOSI)PB5_1") (pintype "bidirectional"))
      (node (ref "ISP") (pin "4") (pinfunction "MOSI_4") (pintype "output"))
    )
    (net (code "24") (name "MOTL_PWM") (class "Default")
      (node (ref "IC3") (pin "16") (pinfunction "(PCINT31/OC2A)PD7_16") (pintype "bidirectional"))
      (node (ref "IC9") (pin "12") (pinfunction "I0_12") (pintype "input"))
      (node (ref "IC9") (pin "9") (pinfunction "I0_9") (pintype "input"))
      (node (ref "R30") (pin "2") (pinfunction "2_2") (pintype "passive"))
    )
    (net (code "25") (name "MOTR_PWM") (class "Default")
      (node (ref "IC3") (pin "15") (pinfunction "(PCINT30/OC2B/ICP)PD6_15") (pintype "bidirectional"))
      (node (ref "IC9") (pin "1") (pinfunction "I0_1") (pintype "input"))
      (node (ref "IC9") (pin "4") (pinfunction "I0_4") (pintype "input"))
      (node (ref "R29") (pin "2") (pinfunction "2_2") (pintype "passive"))
    )
    (net (code "26") (name "Net-(IC2-GND)") (class "Default")
      (node (ref "IC2") (pin "1") (pinfunction "GND_1") (pintype "power_in"))
      (node (ref "R7") (pin "1") (pinfunction "1_1") (pintype "passive"))
      (node (ref "R8") (pin "1") (pinfunction "E_1") (pintype "passive"))
      (node (ref "R8") (pin "2") (pinfunction "S_2") (pintype "passive"))
    )
    (net (code "27") (name "Net-(IC3-(PCINT29{slash}OC1A)PD5)") (class "Default")
      (node (ref "IC3") (pin "14") (pinfunction "(PCINT29/OC1A)PD5_14") (pintype "bidirectional"))
      (node (ref "Q4") (pin "1") (pinfunction "G_1") (pintype "passive"))
      (node (ref "R15") (pin "2") (pinfunction "2_2") (pintype "passive"))
    )
    (net (code "28") (name "Net-(IC3-AREF)") (class "Default")
      (node (ref "C11") (pin "1") (pinfunction "1_1") (pintype "passive"))
      (node (ref "IC3") (pin "29") (pinfunction "AREF_29") (pintype "passive"))
    )
    (net (code "29") (name "Net-(IC3-XTAL1)") (class "Default")
      (node (ref "C10") (pin "1") (pinfunction "1_1") (pintype "passive"))
      (node (ref "IC3") (pin "8") (pinfunction "XTAL1_8") (pintype "bidirectional"))
      (node (ref "Q2") (pin "P$1") (pinfunction "1_P$1") (pintype "passive"))
    )
    (net (code "30") (name "Net-(IC3-XTAL2)") (class "Default")
      (node (ref "C9") (pin "1") (pinfunction "1_1") (pintype "passive"))
      (node (ref "IC3") (pin "7") (pinfunction "XTAL2_7") (pintype "bidirectional"))
      (node (ref "Q2") (pin "P$3") (pinfunction "2_P$3") (pintype "passive"))
    )
    (net (code "31") (name "Net-(IC4-A)") (class "Default")
      (node (ref "IC4") (pin "1") (pinfunction "A_1") (pintype "bidirectional"))
      (node (ref "R19") (pin "1") (pinfunction "1_1") (pintype "passive"))
    )
    (net (code "32") (name "Net-(IC4-K)") (class "Default")
      (node (ref "IC4") (pin "2") (pinfunction "K_2") (pintype "bidirectional"))
      (node (ref "IC5") (pin "2") (pinfunction "K_2") (pintype "bidirectional"))
      (node (ref "IC6") (pin "2") (pinfunction "K_2") (pintype "bidirectional"))
      (node (ref "IC7") (pin "2") (pinfunction "K_2") (pintype "bidirectional"))
      (node (ref "IC8") (pin "2") (pinfunction "K_2") (pintype "bidirectional"))
      (node (ref "Q5") (pin "3") (pinfunction "D_3") (pintype "passive"))
    )
    (net (code "33") (name "Net-(IC5-A)") (class "Default")
      (node (ref "IC5") (pin "1") (pinfunction "A_1") (pintype "bidirectional"))
      (node (ref "R21") (pin "1") (pinfunction "1_1") (pintype "passive"))
    )
    (net (code "34") (name "Net-(IC6-A)") (class "Default")
      (node (ref "IC6") (pin "1") (pinfunction "A_1") (pintype "bidirectional"))
      (node (ref "R23") (pin "1") (pinfunction "1_1") (pintype "passive"))
    )
    (net (code "35") (name "Net-(IC7-A)") (class "Default")
      (node (ref "IC7") (pin "1") (pinfunction "A_1") (pintype "bidirectional"))
      (node (ref "R25") (pin "1") (pinfunction "1_1") (pintype "passive"))
    )
    (net (code "36") (name "Net-(IC8-A)") (class "Default")
      (node (ref "IC8") (pin "1") (pinfunction "A_1") (pintype "bidirectional"))
      (node (ref "R27") (pin "1") (pinfunction "1_1") (pintype "passive"))
    )
    (net (code "37") (name "Net-(IC9A-O)") (class "Default")
      (node (ref "IC9") (pin "3") (pinfunction "O_3") (pintype "output"))
      (node (ref "U2") (pin "16") (pinfunction "AIN1_16") (pintype "bidirectional"))
    )
    (net (code "38") (name "Net-(IC9B-O)") (class "Default")
      (node (ref "IC9") (pin "6") (pinfunction "O_6") (pintype "output"))
      (node (ref "U2") (pin "15") (pinfunction "AIN2_15") (pintype "bidirectional"))
    )
    (net (code "39") (name "Net-(IC9C-O)") (class "Default")
      (node (ref "IC9") (pin "8") (pinfunction "O_8") (pintype "output"))
      (node (ref "U2") (pin "9") (pinfunction "BIN1_9") (pintype "bidirectional"))
    )
    (net (code "40") (name "Net-(IC9D-O)") (class "Default")
      (node (ref "IC9") (pin "11") (pinfunction "O_11") (pintype "output"))
      (node (ref "U2") (pin "10") (pinfunction "BIN2_10") (pintype "bidirectional"))
    )
    (net (code "41") (name "Net-(IC10-A)") (class "Default")
      (node (ref "IC10") (pin "3") (pinfunction "A_3") (pintype "passive"))
      (node (ref "R33") (pin "1") (pinfunction "1_1") (pintype "passive"))
    )
    (net (code "42") (name "Net-(IC10-COL)") (class "Default")
      (node (ref "IC10") (pin "2") (pinfunction "COL_2") (pintype "passive"))
      (node (ref "IC12") (pin "5") (pinfunction "+IN_5") (pintype "input"))
      (node (ref "R34") (pin "1") (pinfunction "1_1") (pintype "passive"))
      (node (ref "TP4") (pin "TP") (pinfunction "TP_TP") (pintype "input"))
    )
    (net (code "43") (name "Net-(IC11-A)") (class "Default")
      (node (ref "IC11") (pin "3") (pinfunction "A_3") (pintype "passive"))
      (node (ref "R35") (pin "1") (pinfunction "1_1") (pintype "passive"))
    )
    (net (code "44") (name "Net-(IC11-COL)") (class "Default")
      (node (ref "IC11") (pin "2") (pinfunction "COL_2") (pintype "passive"))
      (node (ref "IC12") (pin "3") (pinfunction "+IN_3") (pintype "input"))
      (node (ref "R36") (pin "1") (pinfunction "1_1") (pintype "passive"))
    )
    (net (code "45") (name "Net-(IC12A--IN)") (class "Default")
      (node (ref "IC12") (pin "2") (pinfunction "-IN_2") (pintype "input"))
      (node (ref "R38") (pin "2") (pinfunction "S_2") (pintype "passive"))
    )
    (net (code "46") (name "Net-(IC12B--IN)") (class "Default")
      (node (ref "IC12") (pin "6") (pinfunction "-IN_6") (pintype "input"))
      (node (ref "R37") (pin "2") (pinfunction "S_2") (pintype "passive"))
    )
    (net (code "47") (name "Net-(J1B-S)") (class "Default")
      (node (ref "J1") (pin "2") (pinfunction "S_2") (pintype "passive"))
      (node (ref "J2") (pin "1") (pinfunction "S_1") (pintype "passive"))
    )
    (net (code "48") (name "Net-(J2B-S)") (class "Default")
      (node (ref "J2") (pin "2") (pinfunction "S_2") (pintype "passive"))
      (node (ref "JP1") (pin "1") (pinfunction "1_1") (pintype "passive"))
      (node (ref "S1") (pin "2") (pinfunction "P_2") (pintype "passive"))
    )
    (net (code "49") (name "Net-(LED1-PadA)") (class "Default")
      (node (ref "LED1") (pin "A") (pinfunction "A_A") (pintype "passive"))
      (node (ref "R1") (pin "1") (pinfunction "1_1") (pintype "passive"))
    )
    (net (code "50") (name "Net-(LED1-PadC)") (class "Default")
      (node (ref "LED1") (pin "C") (pinfunction "C_C") (pintype "passive"))
      (node (ref "LED3") (pin "A") (pinfunction "A_A") (pintype "passive"))
    )
    (net (code "51") (name "Net-(LED2-PadA)") (class "Default")
      (node (ref "LED2") (pin "A") (pinfunction "A_A") (pintype "passive"))
      (node (ref "R2") (pin "1") (pinfunction "1_1") (pintype "passive"))
    )
    (net (code "52") (name "Net-(LED2-PadC)") (class "Default")
      (node (ref "LED2") (pin "C") (pinfunction "C_C") (pintype "passive"))
      (node (ref "LED4") (pin "A") (pinfunction "A_A") (pintype "passive"))
    )
    (net (code "53") (name "Net-(MOT_FLT-PadA)") (class "Default")
      (node (ref "MOT_FLT") (pin "A") (pinfunction "A_A") (pintype "passive"))
      (node (ref "R31") (pin "2") (pinfunction "2_2") (pintype "passive"))
    )
    (net (code "54") (name "Net-(PWR-PadA)") (class "Default")
      (node (ref "PWR") (pin "A") (pinfunction "A_A") (pintype "passive"))
      (node (ref "R4") (pin "1") (pinfunction "1_1") (pintype "passive"))
    )
    (net (code "55") (name "Net-(Q1-D)") (class "Default")
      (node (ref "LED3") (pin "C") (pinfunction "C_C") (pintype "passive"))
      (node (ref "LED4") (pin "C") (pinfunction "C_C") (pintype "passive"))
      (node (ref "Q1") (pin "3") (pinfunction "D_3") (pintype "passive"))
    )
    (net (code "56") (name "Net-(Q4-D)") (class "Default")
      (node (ref "Q4") (pin "3") (pinfunction "D_3") (pintype "passive"))
      (node (ref "SP1") (pin "-") (pinfunction "2_-") (pintype "passive"))
    )
    (net (code "57") (name "Net-(Q6-PadD)") (class "Default")
      (node (ref "Q6") (pin "D") (pinfunction "D_D") (pintype "passive"))
      (node (ref "R33") (pin "2") (pinfunction "2_2") (pintype "passive"))
      (node (ref "R34") (pin "2") (pinfunction "2_2") (pintype "passive"))
      (node (ref "R35") (pin "2") (pinfunction "2_2") (pintype "passive"))
      (node (ref "R36") (pin "2") (pinfunction "2_2") (pintype "passive"))
    )
    (net (code "58") (name "Net-(R17-Pad1)") (class "Default")
      (node (ref "R17") (pin "1") (pinfunction "1_1") (pintype "passive"))
      (node (ref "SJ2") (pin "1") (pinfunction "1_1") (pintype "passive"))
    )
    (net (code "59") (name "Net-(STATUSA-C)") (class "Default")
      (node (ref "R10") (pin "2") (pinfunction "2_2") (pintype "passive"))
      (node (ref "STATUS") (pin "1") (pinfunction "C_1") (pintype "passive"))
    )
    (net (code "60") (name "Net-(STATUSB-C)") (class "Default")
      (node (ref "R11") (pin "2") (pinfunction "2_2") (pintype "passive"))
      (node (ref "STATUS") (pin "3") (pinfunction "C_3") (pintype "passive"))
    )
    (net (code "61") (name "Net-(U$1-L_MOTOR_A)") (class "Default")
      (node (ref "U$1") (pin "1") (pinfunction "L_MOTOR_A_1") (pintype "bidirectional"))
      (node (ref "U2") (pin "2") (pinfunction "AOUT1_2") (pintype "bidirectional"))
    )
    (net (code "62") (name "Net-(U$1-L_MOTOR_B)") (class "Default")
      (node (ref "U$1") (pin "2") (pinfunction "L_MOTOR_B_2") (pintype "bidirectional"))
      (node (ref "U2") (pin "4") (pinfunction "AOUT2_4") (pintype "bidirectional"))
    )
    (net (code "63") (name "Net-(U$1-R_MOTOR_A)") (class "Default")
      (node (ref "U$1") (pin "3") (pinfunction "R_MOTOR_A_3") (pintype "bidirectional"))
      (node (ref "U2") (pin "5") (pinfunction "BOUT2_5") (pintype "bidirectional"))
    )
    (net (code "64") (name "Net-(U$1-R_MOTOR_B)") (class "Default")
      (node (ref "U$1") (pin "4") (pinfunction "R_MOTOR_B_4") (pintype "bidirectional"))
      (node (ref "U2") (pin "7") (pinfunction "BOUT1_7") (pintype "bidirectional"))
    )
    (net (code "65") (name "Net-(U1-VCC)") (class "Default")
      (node (ref "Q3") (pin "D") (pinfunction "D_D") (pintype "passive"))
      (node (ref "U1") (pin "2") (pinfunction "VCC_2") (pintype "bidirectional"))
    )
    (net (code "66") (name "Net-(U2-NFAULT)") (class "Default")
      (node (ref "MOT_FLT") (pin "C") (pinfunction "C_C") (pintype "passive"))
      (node (ref "U2") (pin "8") (pinfunction "NFAULT_8") (pintype "bidirectional"))
    )
    (net (code "67") (name "Net-(U2-VCP)") (class "Default")
      (node (ref "C17") (pin "2") (pinfunction "2_2") (pintype "passive"))
      (node (ref "U2") (pin "11") (pinfunction "VCP_11") (pintype "bidirectional"))
    )
    (net (code "68") (name "Net-(U2-VINT)") (class "Default")
      (node (ref "C18") (pin "1") (pinfunction "1_1") (pintype "passive"))
      (node (ref "U2") (pin "14") (pinfunction "VINT_14") (pintype "bidirectional"))
    )
    (net (code "69") (name "PA0{slash}ADC0") (class "Default")
      (node (ref "BUS1") (pin "6") (pinfunction "6_6") (pintype "passive"))
      (node (ref "IC3") (pin "37") (pinfunction "(PCINT0/ADC0)PA0_37") (pintype "bidirectional"))
    )
    (net (code "70") (name "PA1{slash}ADC1") (class "Default")
      (node (ref "BUS1") (pin "7") (pinfunction "7_7") (pintype "passive"))
      (node (ref "IC3") (pin "36") (pinfunction "(PCINT1/ADC1)PA1_36") (pintype "bidirectional"))
    )
    (net (code "71") (name "RESET") (class "Default")
      (node (ref "BUS2") (pin "2") (pinfunction "2_2") (pintype "passive"))
      (node (ref "C8") (pin "1") (pinfunction "1_1") (pintype "passive"))
      (node (ref "IC3") (pin "4") (pinfunction "RESET_4") (pintype "input"))
      (node (ref "ISP") (pin "5") (pinfunction "RST_5") (pintype "output"))
      (node (ref "R9") (pin "1") (pinfunction "1_1") (pintype "passive"))
      (node (ref "SW3") (pin "1") (pinfunction "1_1") (pintype "bidirectional"))
      (node (ref "U2") (pin "1") (pinfunction "NSLEEP_1") (pintype "bidirectional"))
    )
    (net (code "72") (name "RXD") (class "Default")
      (node (ref "BUS2") (pin "6") (pinfunction "6_6") (pintype "passive"))
      (node (ref "IC3") (pin "9") (pinfunction "(PCINT24/RXD0)PD0_9") (pintype "bidirectional"))
      (node (ref "U1") (pin "4") (pinfunction "TXD_4") (pintype "bidirectional"))
    )
    (net (code "73") (name "SCK") (class "Default")
      (node (ref "BUS2") (pin "3") (pinfunction "3_3") (pintype "passive"))
      (node (ref "IC3") (pin "3") (pinfunction "(PCINT15/SCK)PB7_3") (pintype "bidirectional"))
      (node (ref "ISP") (pin "3") (pinfunction "SCK_3") (pintype "output"))
    )
    (net (code "74") (name "SCL") (class "Default")
      (node (ref "BUS1") (pin "4") (pinfunction "4_4") (pintype "passive"))
      (node (ref "IC3") (pin "19") (pinfunction "(PCINT16/SCL)PC0_19") (pintype "output"))
      (node (ref "R13") (pin "1") (pinfunction "1_1") (pintype "passive"))
    )
    (net (code "75") (name "SDA") (class "Default")
      (node (ref "BUS1") (pin "5") (pinfunction "5_5") (pintype "passive"))
      (node (ref "IC3") (pin "20") (pinfunction "(PCINT17/SDA)PC1_20") (pintype "output"))
      (node (ref "R12") (pin "1") (pinfunction "1_1") (pintype "passive"))
    )
    (net (code "76") (name "START") (class "Default")
      (node (ref "BUS1") (pin "3") (pinfunction "3_3") (pintype "passive"))
      (node (ref "IC3") (pin "42") (pinfunction "(PCINT10/INT2/AIN0)PB2_42") (pintype "bidirectional"))
      (node (ref "SW1") (pin "4") (pinfunction "4_4") (pintype "bidirectional"))
    )
    (net (code "77") (name "TXD") (class "Default")
      (node (ref "BUS2") (pin "7") (pinfunction "7_7") (pintype "passive"))
      (node (ref "IC3") (pin "10") (pinfunction "(PCINT25/TXD0)PD1_10") (pintype "bidirectional"))
      (node (ref "R16") (pin "2") (pinfunction "2_2") (pintype "passive"))
    )
    (net (code "78") (name "TXD_3V3") (class "Default")
      (node (ref "R16") (pin "1") (pinfunction "1_1") (pintype "passive"))
      (node (ref "R17") (pin "2") (pinfunction "2_2") (pintype "passive"))
      (node (ref "U1") (pin "5") (pinfunction "RXD_5") (pintype "bidirectional"))
    )
    (net (code "79") (name "USER") (class "Default")
      (node (ref "IC3") (pin "43") (pinfunction "(PCINT11/OC0A/AIN1)PB3_43") (pintype "bidirectional"))
      (node (ref "SW2") (pin "4") (pinfunction "4_4") (pintype "bidirectional"))
    )
    (net (code "80") (name "V+") (class "Default")
      (node (ref "BUS1") (pin "2") (pinfunction "2_2") (pintype "passive"))
      (node (ref "C1") (pin "+") (pinfunction "+_+") (pintype "passive"))
      (node (ref "C2") (pin "1") (pinfunction "1_1") (pintype "passive"))
      (node (ref "C6") (pin "1") (pinfunction "1_1") (pintype "passive"))
      (node (ref "IC1") (pin "3") (pinfunction "VIN_3") (pintype "input"))
      (node (ref "IC2") (pin "3") (pinfunction "VIN_3") (pintype "input"))
      (node (ref "R1") (pin "2") (pinfunction "2_2") (pintype "passive"))
      (node (ref "R2") (pin "2") (pinfunction "2_2") (pintype "passive"))
      (node (ref "R3") (pin "2") (pinfunction "2_2") (pintype "passive"))
      (node (ref "S1") (pin "3") (pinfunction "S_3") (pintype "passive"))
    )
    (net (code "81") (name "VBAT") (class "Default")
      (node (ref "IC3") (pin "35") (pinfunction "(PCINT2/ADC2)PA2_35") (pintype "bidirectional"))
      (node (ref "R3") (pin "1") (pinfunction "1_1") (pintype "passive"))
      (node (ref "R5") (pin "2") (pinfunction "2_2") (pintype "passive"))
    )
    (net (code "82") (name "VPP") (class "Default")
      (node (ref "C15") (pin "1") (pinfunction "1_1") (pintype "passive"))
      (node (ref "C16") (pin "1") (pinfunction "1_1") (pintype "passive"))
      (node (ref "C17") (pin "1") (pinfunction "1_1") (pintype "passive"))
      (node (ref "C7") (pin "+") (pinfunction "+_+") (pintype "passive"))
      (node (ref "IC2") (pin "2") (pinfunction "VOUT_2") (pintype "output"))
      (node (ref "R31") (pin "1") (pinfunction "1_1") (pintype "passive"))
      (node (ref "R7") (pin "2") (pinfunction "2_2") (pintype "passive"))
      (node (ref "U2") (pin "12") (pinfunction "VM_12") (pintype "bidirectional"))
    )
    (net (code "83") (name "unconnected-(S1-O-Pad1)") (class "Default")
      (node (ref "S1") (pin "1") (pinfunction "O_1") (pintype "passive"))
    )
    (net (code "84") (name "unconnected-(SW1-Pad2)") (class "Default")
      (node (ref "SW1") (pin "2") (pinfunction "2_2") (pintype "bidirectional"))
    )
    (net (code "85") (name "unconnected-(SW1-Pad3)") (class "Default")
      (node (ref "SW1") (pin "3") (pinfunction "3_3") (pintype "bidirectional"))
    )
    (net (code "86") (name "unconnected-(SW1-Pad5)") (class "Default")
      (node (ref "SW1") (pin "5") (pinfunction "5_5") (pintype "bidirectional"))
    )
    (net (code "87") (name "unconnected-(SW2-Pad2)") (class "Default")
      (node (ref "SW2") (pin "2") (pinfunction "2_2") (pintype "bidirectional"))
    )
    (net (code "88") (name "unconnected-(SW2-Pad3)") (class "Default")
      (node (ref "SW2") (pin "3") (pinfunction "3_3") (pintype "bidirectional"))
    )
    (net (code "89") (name "unconnected-(SW2-Pad5)") (class "Default")
      (node (ref "SW2") (pin "5") (pinfunction "5_5") (pintype "bidirectional"))
    )
    (net (code "90") (name "unconnected-(SW3-Pad2)") (class "Default")
      (node (ref "SW3") (pin "2") (pinfunction "2_2") (pintype "bidirectional"))
    )
    (net (code "91") (name "unconnected-(SW3-Pad3)") (class "Default")
      (node (ref "SW3") (pin "3") (pinfunction "3_3") (pintype "bidirectional"))
    )
    (net (code "92") (name "unconnected-(SW3-Pad5)") (class "Default")
      (node (ref "SW3") (pin "5") (pinfunction "5_5") (pintype "bidirectional"))
    )
    (net (code "93") (name "unconnected-(U1-EN-Pad1)") (class "Default")
      (node (ref "U1") (pin "1") (pinfunction "EN_1") (pintype "bidirectional"))
    )
    (net (code "94") (name "unconnected-(U1-STATE-Pad6)") (class "Default")
      (node (ref "U1") (pin "6") (pinfunction "STATE_6") (pintype "bidirectional"))
    )
  )
)
